# podlewacz_v4.net
KiCad netlist of a schematic drawn in EAGLE
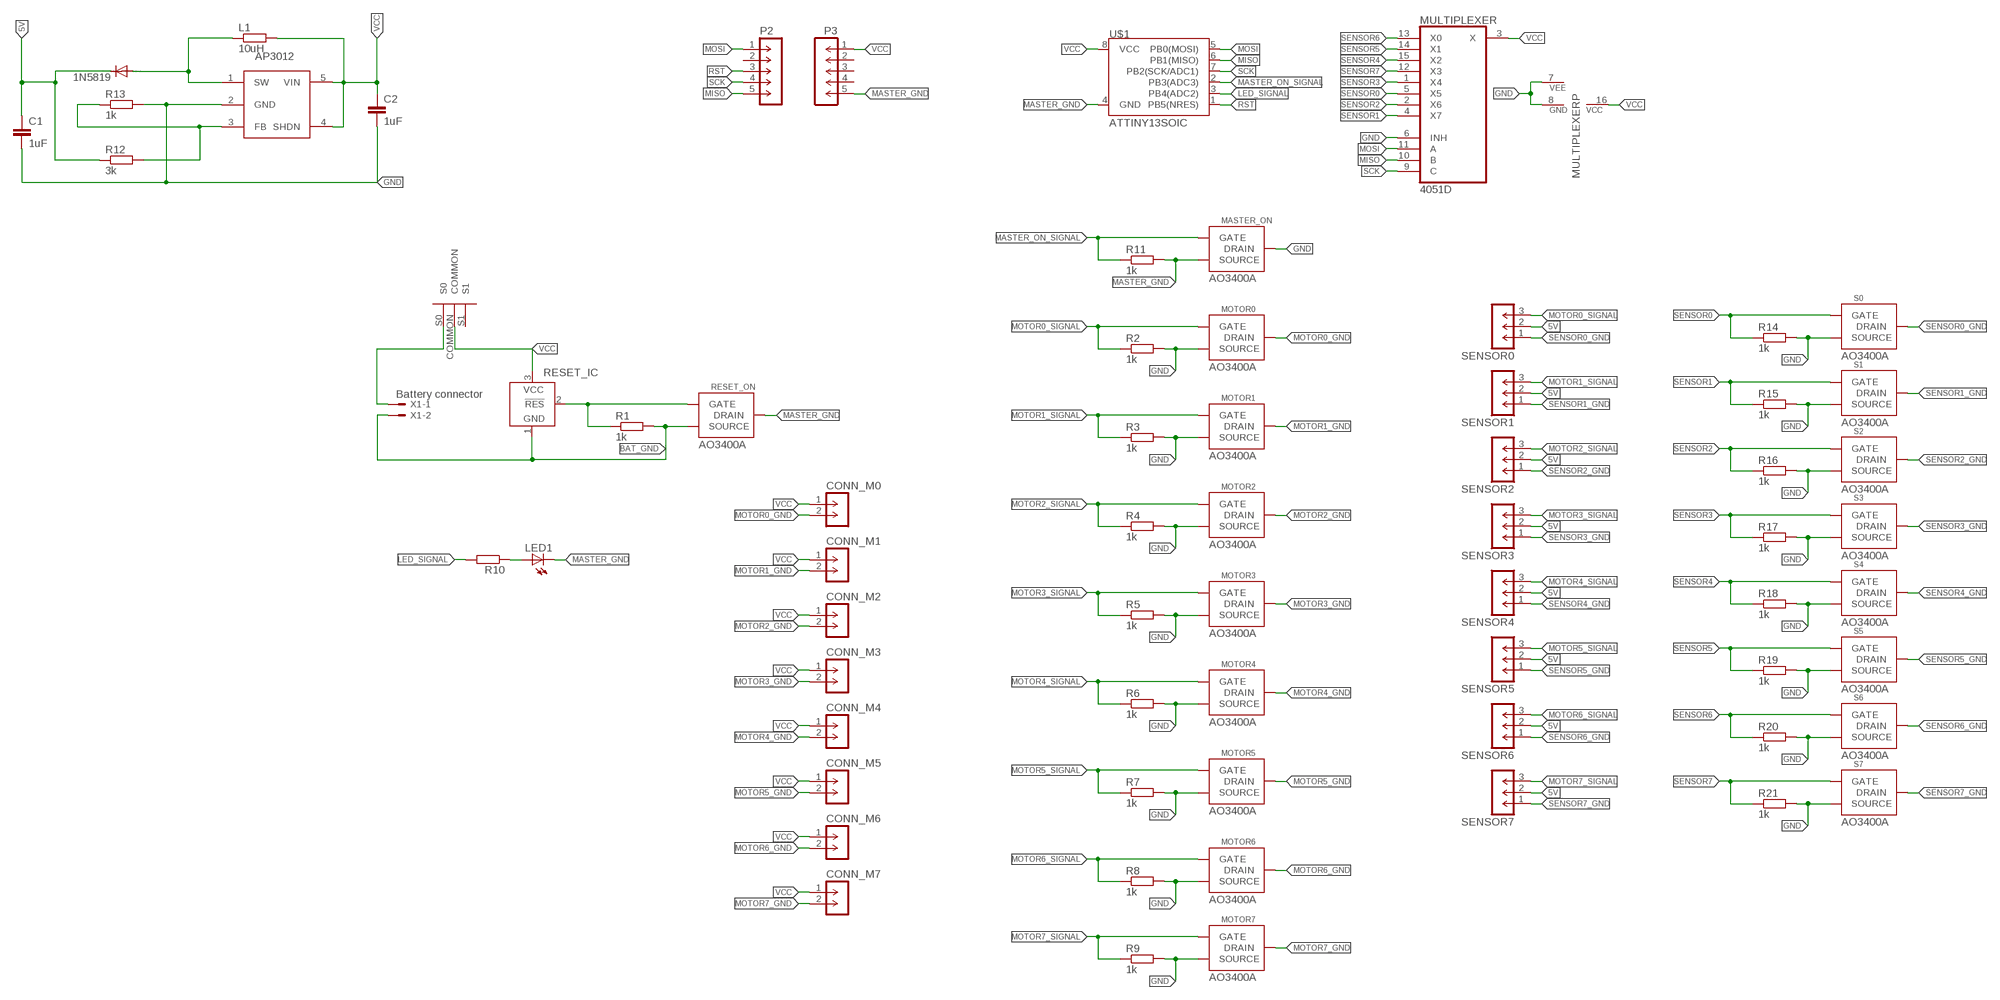
[diagram p0: schematic, sheet 1]

(export (version "E")
  (design (tool "Eeschema 10.0.6"))
  (components
    (comp (ref "1N5819")
      (value "DIODE-DO214AC")
      (footprint "eagle-import:DO214AC")
      (libsource (lib "eagle-import") (part "DIODE-DO214AC"))
    )
    (comp (ref "AP3012")
      (value "AP3012")
      (footprint "eagle-import:SOT-23-5")
      (libsource (lib "eagle-import") (part "AP3012"))
    )
    (comp (ref "C1")
      (value "1uF")
      (footprint "eagle-import:C1206")
      (libsource (lib "eagle-import") (part "C-EUC1206"))
    )
    (comp (ref "C2")
      (value "1uF")
      (footprint "eagle-import:C1206")
      (libsource (lib "eagle-import") (part "C-EUC1206"))
    )
    (comp (ref "CONN_M0")
      (value "M-1X02-SIP-100-32Y")
      (footprint "eagle-import:SIP-100-02-32Y")
      (libsource (lib "eagle-import") (part "M-1X02-SIP-100-32Y"))
    )
    (comp (ref "CONN_M1")
      (value "M-1X02-SIP-100-32Y")
      (footprint "eagle-import:SIP-100-02-32Y")
      (libsource (lib "eagle-import") (part "M-1X02-SIP-100-32Y"))
    )
    (comp (ref "CONN_M2")
      (value "M-1X02-SIP-100-32Y")
      (footprint "eagle-import:SIP-100-02-32Y")
      (libsource (lib "eagle-import") (part "M-1X02-SIP-100-32Y"))
    )
    (comp (ref "CONN_M3")
      (value "M-1X02-SIP-100-32Y")
      (footprint "eagle-import:SIP-100-02-32Y")
      (libsource (lib "eagle-import") (part "M-1X02-SIP-100-32Y"))
    )
    (comp (ref "CONN_M4")
      (value "M-1X02-SIP-100-32Y")
      (footprint "eagle-import:SIP-100-02-32Y")
      (libsource (lib "eagle-import") (part "M-1X02-SIP-100-32Y"))
    )
    (comp (ref "CONN_M5")
      (value "M-1X02-SIP-100-32Y")
      (footprint "eagle-import:SIP-100-02-32Y")
      (libsource (lib "eagle-import") (part "M-1X02-SIP-100-32Y"))
    )
    (comp (ref "CONN_M6")
      (value "M-1X02-SIP-100-32Y")
      (footprint "eagle-import:SIP-100-02-32Y")
      (libsource (lib "eagle-import") (part "M-1X02-SIP-100-32Y"))
    )
    (comp (ref "CONN_M7")
      (value "M-1X02-SIP-100-32Y")
      (footprint "eagle-import:SIP-100-02-32Y")
      (libsource (lib "eagle-import") (part "M-1X02-SIP-100-32Y"))
    )
    (comp (ref "L1")
      (value "10uH")
      (footprint "eagle-import:R0805")
      (libsource (lib "eagle-import") (part "R-EU_R0805"))
    )
    (comp (ref "LED1")
      (value "LEDCHIP-LED0805")
      (footprint "eagle-import:CHIP-LED0805")
      (libsource (lib "eagle-import") (part "LEDCHIP-LED0805"))
    )
    (comp (ref "MASTER_ON")
      (value "AO3400A")
      (footprint "eagle-import:SOT-23")
      (libsource (lib "eagle-import") (part "AO3400A"))
    )
    (comp (ref "MOTOR0")
      (value "AO3400A")
      (footprint "eagle-import:SOT-23")
      (libsource (lib "eagle-import") (part "AO3400A"))
    )
    (comp (ref "MOTOR1")
      (value "AO3400A")
      (footprint "eagle-import:SOT-23")
      (libsource (lib "eagle-import") (part "AO3400A"))
    )
    (comp (ref "MOTOR2")
      (value "AO3400A")
      (footprint "eagle-import:SOT-23")
      (libsource (lib "eagle-import") (part "AO3400A"))
    )
    (comp (ref "MOTOR3")
      (value "AO3400A")
      (footprint "eagle-import:SOT-23")
      (libsource (lib "eagle-import") (part "AO3400A"))
    )
    (comp (ref "MOTOR4")
      (value "AO3400A")
      (footprint "eagle-import:SOT-23")
      (libsource (lib "eagle-import") (part "AO3400A"))
    )
    (comp (ref "MOTOR5")
      (value "AO3400A")
      (footprint "eagle-import:SOT-23")
      (libsource (lib "eagle-import") (part "AO3400A"))
    )
    (comp (ref "MOTOR6")
      (value "AO3400A")
      (footprint "eagle-import:SOT-23")
      (libsource (lib "eagle-import") (part "AO3400A"))
    )
    (comp (ref "MOTOR7")
      (value "AO3400A")
      (footprint "eagle-import:SOT-23")
      (libsource (lib "eagle-import") (part "AO3400A"))
    )
    (comp (ref "MULTIPLEXER")
      (value "4051D")
      (footprint "eagle-import:SO16")
      (libsource (lib "eagle-import") (part "4051D"))
    )
    (comp (ref "P2")
      (value "M-1X05-SIP-100-32")
      (footprint "eagle-import:SIP-100-05-32")
      (libsource (lib "eagle-import") (part "M-1X05-SIP-100-32"))
    )
    (comp (ref "P3")
      (value "M-1X05-SIP-100-32")
      (footprint "eagle-import:SIP-100-05-32")
      (libsource (lib "eagle-import") (part "M-1X05-SIP-100-32"))
    )
    (comp (ref "R1")
      (value "1k")
      (footprint "eagle-import:M1206")
      (libsource (lib "eagle-import") (part "R-EU_M1206"))
    )
    (comp (ref "R2")
      (value "1k")
      (footprint "eagle-import:M1206")
      (libsource (lib "eagle-import") (part "R-EU_M1206"))
    )
    (comp (ref "R3")
      (value "1k")
      (footprint "eagle-import:M1206")
      (libsource (lib "eagle-import") (part "R-EU_M1206"))
    )
    (comp (ref "R4")
      (value "1k")
      (footprint "eagle-import:M1206")
      (libsource (lib "eagle-import") (part "R-EU_M1206"))
    )
    (comp (ref "R5")
      (value "1k")
      (footprint "eagle-import:M1206")
      (libsource (lib "eagle-import") (part "R-EU_M1206"))
    )
    (comp (ref "R6")
      (value "1k")
      (footprint "eagle-import:M1206")
      (libsource (lib "eagle-import") (part "R-EU_M1206"))
    )
    (comp (ref "R7")
      (value "1k")
      (footprint "eagle-import:M1206")
      (libsource (lib "eagle-import") (part "R-EU_M1206"))
    )
    (comp (ref "R8")
      (value "1k")
      (footprint "eagle-import:M1206")
      (libsource (lib "eagle-import") (part "R-EU_M1206"))
    )
    (comp (ref "R9")
      (value "1k")
      (footprint "eagle-import:M1206")
      (libsource (lib "eagle-import") (part "R-EU_M1206"))
    )
    (comp (ref "R10")
      (value "R-EU_M0805")
      (footprint "eagle-import:M0805")
      (libsource (lib "eagle-import") (part "R-EU_M0805"))
    )
    (comp (ref "R11")
      (value "1k")
      (footprint "eagle-import:M1206")
      (libsource (lib "eagle-import") (part "R-EU_M1206"))
    )
    (comp (ref "R12")
      (value "3k")
      (footprint "eagle-import:M1206")
      (libsource (lib "eagle-import") (part "R-EU_M1206"))
    )
    (comp (ref "R13")
      (value "1k")
      (footprint "eagle-import:M1206")
      (libsource (lib "eagle-import") (part "R-EU_M1206"))
    )
    (comp (ref "R14")
      (value "1k")
      (footprint "eagle-import:M1206")
      (libsource (lib "eagle-import") (part "R-EU_M1206"))
    )
    (comp (ref "R15")
      (value "1k")
      (footprint "eagle-import:M1206")
      (libsource (lib "eagle-import") (part "R-EU_M1206"))
    )
    (comp (ref "R16")
      (value "1k")
      (footprint "eagle-import:M1206")
      (libsource (lib "eagle-import") (part "R-EU_M1206"))
    )
    (comp (ref "R17")
      (value "1k")
      (footprint "eagle-import:M1206")
      (libsource (lib "eagle-import") (part "R-EU_M1206"))
    )
    (comp (ref "R18")
      (value "1k")
      (footprint "eagle-import:M1206")
      (libsource (lib "eagle-import") (part "R-EU_M1206"))
    )
    (comp (ref "R19")
      (value "1k")
      (footprint "eagle-import:M1206")
      (libsource (lib "eagle-import") (part "R-EU_M1206"))
    )
    (comp (ref "R20")
      (value "1k")
      (footprint "eagle-import:M1206")
      (libsource (lib "eagle-import") (part "R-EU_M1206"))
    )
    (comp (ref "R21")
      (value "1k")
      (footprint "eagle-import:M1206")
      (libsource (lib "eagle-import") (part "R-EU_M1206"))
    )
    (comp (ref "RESET_IC")
      (value "TCM809")
      (footprint "eagle-import:SOT23B-3")
      (fields (field (name "MF") "MICROCHIP") (field (name "MPN") "TCM809MENB713"))
      (libsource (lib "eagle-import") (part "TCM809"))
    )
    (comp (ref "RESET_ON")
      (value "AO3400A")
      (footprint "eagle-import:SOT-23")
      (libsource (lib "eagle-import") (part "AO3400A"))
    )
    (comp (ref "S0")
      (value "AO3400A")
      (footprint "eagle-import:SOT-23")
      (libsource (lib "eagle-import") (part "AO3400A"))
    )
    (comp (ref "S1")
      (value "AO3400A")
      (footprint "eagle-import:SOT-23")
      (libsource (lib "eagle-import") (part "AO3400A"))
    )
    (comp (ref "S2")
      (value "AO3400A")
      (footprint "eagle-import:SOT-23")
      (libsource (lib "eagle-import") (part "AO3400A"))
    )
    (comp (ref "S3")
      (value "AO3400A")
      (footprint "eagle-import:SOT-23")
      (libsource (lib "eagle-import") (part "AO3400A"))
    )
    (comp (ref "S4")
      (value "AO3400A")
      (footprint "eagle-import:SOT-23")
      (libsource (lib "eagle-import") (part "AO3400A"))
    )
    (comp (ref "S5")
      (value "AO3400A")
      (footprint "eagle-import:SOT-23")
      (libsource (lib "eagle-import") (part "AO3400A"))
    )
    (comp (ref "S6")
      (value "AO3400A")
      (footprint "eagle-import:SOT-23")
      (libsource (lib "eagle-import") (part "AO3400A"))
    )
    (comp (ref "S7")
      (value "AO3400A")
      (footprint "eagle-import:SOT-23")
      (libsource (lib "eagle-import") (part "AO3400A"))
    )
    (comp (ref "SENSOR0")
      (value "M-1X03-SIP-100-32Y")
      (footprint "eagle-import:SIP-100-03-32Y")
      (libsource (lib "eagle-import") (part "M-1X03-SIP-100-32Y"))
    )
    (comp (ref "SENSOR1")
      (value "M-1X03-SIP-100-32Y")
      (footprint "eagle-import:SIP-100-03-32Y")
      (libsource (lib "eagle-import") (part "M-1X03-SIP-100-32Y"))
    )
    (comp (ref "SENSOR2")
      (value "M-1X03-SIP-100-32Y")
      (footprint "eagle-import:SIP-100-03-32Y")
      (libsource (lib "eagle-import") (part "M-1X03-SIP-100-32Y"))
    )
    (comp (ref "SENSOR3")
      (value "M-1X03-SIP-100-32Y")
      (footprint "eagle-import:SIP-100-03-32Y")
      (libsource (lib "eagle-import") (part "M-1X03-SIP-100-32Y"))
    )
    (comp (ref "SENSOR4")
      (value "M-1X03-SIP-100-32Y")
      (footprint "eagle-import:SIP-100-03-32Y")
      (libsource (lib "eagle-import") (part "M-1X03-SIP-100-32Y"))
    )
    (comp (ref "SENSOR5")
      (value "M-1X03-SIP-100-32Y")
      (footprint "eagle-import:SIP-100-03-32Y")
      (libsource (lib "eagle-import") (part "M-1X03-SIP-100-32Y"))
    )
    (comp (ref "SENSOR6")
      (value "M-1X03-SIP-100-32Y")
      (footprint "eagle-import:SIP-100-03-32Y")
      (libsource (lib "eagle-import") (part "M-1X03-SIP-100-32Y"))
    )
    (comp (ref "SENSOR7")
      (value "M-1X03-SIP-100-32Y")
      (footprint "eagle-import:SIP-100-03-32Y")
      (libsource (lib "eagle-import") (part "M-1X03-SIP-100-32Y"))
    )
    (comp (ref "U$1")
      (value "ATTINY13SOIC")
      (footprint "eagle-import:SO08")
      (libsource (lib "eagle-import") (part "ATTINY13SOIC"))
    )
    (comp (ref "U$2")
      (value "SPDT_SLIDE_SWITCH_2_PITCH")
      (footprint "eagle-import:SPDT_SLIDE_SWITCH_2_PITCH")
      (libsource (lib "eagle-import") (part "SPDT_SLIDE_SWITCH_2_PITCH"))
    )
    (comp (ref "X1")
      (value "Battery connector")
      (footprint "eagle-import:22-23-2021")
      (fields (field (name "MF") "MOLEX") (field (name "MPN") "22-23-2021"))
      (libsource (lib "eagle-import") (part "22-23-2021"))
    )
  )
  (nets
    (net (code "1") (name "5V") (class "Default")
      (node (ref "1N5819") (pin "C") (pinfunction "C_C") (pintype "passive"))
      (node (ref "C1") (pin "1") (pinfunction "1_1") (pintype "passive"))
      (node (ref "R12") (pin "1") (pinfunction "1_1") (pintype "passive"))
      (node (ref "SENSOR0") (pin "2") (pinfunction "2_2") (pintype "passive"))
      (node (ref "SENSOR1") (pin "2") (pinfunction "2_2") (pintype "passive"))
      (node (ref "SENSOR2") (pin "2") (pinfunction "2_2") (pintype "passive"))
      (node (ref "SENSOR3") (pin "2") (pinfunction "2_2") (pintype "passive"))
      (node (ref "SENSOR4") (pin "2") (pinfunction "2_2") (pintype "passive"))
      (node (ref "SENSOR5") (pin "2") (pinfunction "2_2") (pintype "passive"))
      (node (ref "SENSOR6") (pin "2") (pinfunction "2_2") (pintype "passive"))
      (node (ref "SENSOR7") (pin "2") (pinfunction "2_2") (pintype "passive"))
    )
    (net (code "2") (name "BAT_GND") (class "Default")
      (node (ref "R1") (pin "2") (pinfunction "2_2") (pintype "passive"))
      (node (ref "RESET_IC") (pin "1") (pinfunction "GND_1") (pintype "power_in"))
      (node (ref "RESET_ON") (pin "2") (pinfunction "SOURCE_2") (pintype "bidirectional"))
      (node (ref "X1") (pin "2") (pinfunction "S_2") (pintype "passive"))
    )
    (net (code "3") (name "GND") (class "Default")
      (node (ref "AP3012") (pin "2") (pinfunction "GND_2") (pintype "bidirectional"))
      (node (ref "C1") (pin "2") (pinfunction "2_2") (pintype "passive"))
      (node (ref "C2") (pin "2") (pinfunction "2_2") (pintype "passive"))
      (node (ref "MASTER_ON") (pin "3") (pinfunction "DRAIN_3") (pintype "bidirectional"))
      (node (ref "MOTOR0") (pin "2") (pinfunction "SOURCE_2") (pintype "bidirectional"))
      (node (ref "MOTOR1") (pin "2") (pinfunction "SOURCE_2") (pintype "bidirectional"))
      (node (ref "MOTOR2") (pin "2") (pinfunction "SOURCE_2") (pintype "bidirectional"))
      (node (ref "MOTOR3") (pin "2") (pinfunction "SOURCE_2") (pintype "bidirectional"))
      (node (ref "MOTOR4") (pin "2") (pinfunction "SOURCE_2") (pintype "bidirectional"))
      (node (ref "MOTOR5") (pin "2") (pinfunction "SOURCE_2") (pintype "bidirectional"))
      (node (ref "MOTOR6") (pin "2") (pinfunction "SOURCE_2") (pintype "bidirectional"))
      (node (ref "MOTOR7") (pin "2") (pinfunction "SOURCE_2") (pintype "bidirectional"))
      (node (ref "MULTIPLEXER") (pin "6") (pinfunction "INH_6") (pintype "input"))
      (node (ref "MULTIPLEXER") (pin "7") (pinfunction "VEE_7") (pintype "power_in"))
      (node (ref "MULTIPLEXER") (pin "8") (pinfunction "GND_8") (pintype "power_in"))
      (node (ref "R13") (pin "2") (pinfunction "2_2") (pintype "passive"))
      (node (ref "R14") (pin "2") (pinfunction "2_2") (pintype "passive"))
      (node (ref "R15") (pin "2") (pinfunction "2_2") (pintype "passive"))
      (node (ref "R16") (pin "2") (pinfunction "2_2") (pintype "passive"))
      (node (ref "R17") (pin "2") (pinfunction "2_2") (pintype "passive"))
      (node (ref "R18") (pin "2") (pinfunction "2_2") (pintype "passive"))
      (node (ref "R19") (pin "2") (pinfunction "2_2") (pintype "passive"))
      (node (ref "R2") (pin "2") (pinfunction "2_2") (pintype "passive"))
      (node (ref "R20") (pin "2") (pinfunction "2_2") (pintype "passive"))
      (node (ref "R21") (pin "2") (pinfunction "2_2") (pintype "passive"))
      (node (ref "R3") (pin "2") (pinfunction "2_2") (pintype "passive"))
      (node (ref "R4") (pin "2") (pinfunction "2_2") (pintype "passive"))
      (node (ref "R5") (pin "2") (pinfunction "2_2") (pintype "passive"))
      (node (ref "R6") (pin "2") (pinfunction "2_2") (pintype "passive"))
      (node (ref "R7") (pin "2") (pinfunction "2_2") (pintype "passive"))
      (node (ref "R8") (pin "2") (pinfunction "2_2") (pintype "passive"))
      (node (ref "R9") (pin "2") (pinfunction "2_2") (pintype "passive"))
      (node (ref "S0") (pin "2") (pinfunction "SOURCE_2") (pintype "bidirectional"))
      (node (ref "S1") (pin "2") (pinfunction "SOURCE_2") (pintype "bidirectional"))
      (node (ref "S2") (pin "2") (pinfunction "SOURCE_2") (pintype "bidirectional"))
      (node (ref "S3") (pin "2") (pinfunction "SOURCE_2") (pintype "bidirectional"))
      (node (ref "S4") (pin "2") (pinfunction "SOURCE_2") (pintype "bidirectional"))
      (node (ref "S5") (pin "2") (pinfunction "SOURCE_2") (pintype "bidirectional"))
      (node (ref "S6") (pin "2") (pinfunction "SOURCE_2") (pintype "bidirectional"))
      (node (ref "S7") (pin "2") (pinfunction "SOURCE_2") (pintype "bidirectional"))
    )
    (net (code "4") (name "LED_SIGNAL") (class "Default")
      (node (ref "R10") (pin "2") (pinfunction "2_2") (pintype "passive"))
      (node (ref "U$1") (pin "3") (pinfunction "PB4(ADC2)_3") (pintype "bidirectional"))
    )
    (net (code "5") (name "MASTER_GND") (class "Default")
      (node (ref "LED1") (pin "C") (pinfunction "C_C") (pintype "passive"))
      (node (ref "MASTER_ON") (pin "2") (pinfunction "SOURCE_2") (pintype "bidirectional"))
      (node (ref "P3") (pin "5") (pinfunction "5_5") (pintype "passive"))
      (node (ref "R11") (pin "2") (pinfunction "2_2") (pintype "passive"))
      (node (ref "RESET_ON") (pin "3") (pinfunction "DRAIN_3") (pintype "bidirectional"))
      (node (ref "U$1") (pin "4") (pinfunction "GND_4") (pintype "bidirectional"))
    )
    (net (code "6") (name "MASTER_ON_SIGNAL") (class "Default")
      (node (ref "MASTER_ON") (pin "1") (pinfunction "GATE_1") (pintype "bidirectional"))
      (node (ref "R11") (pin "1") (pinfunction "1_1") (pintype "passive"))
      (node (ref "U$1") (pin "2") (pinfunction "PB3(ADC3)_2") (pintype "bidirectional"))
    )
    (net (code "7") (name "MISO") (class "Default")
      (node (ref "MULTIPLEXER") (pin "10") (pinfunction "B_10") (pintype "input"))
      (node (ref "P2") (pin "5") (pinfunction "5_5") (pintype "passive"))
      (node (ref "U$1") (pin "6") (pinfunction "PB1(MISO)_6") (pintype "bidirectional"))
    )
    (net (code "8") (name "MOSI") (class "Default")
      (node (ref "MULTIPLEXER") (pin "11") (pinfunction "A_11") (pintype "input"))
      (node (ref "P2") (pin "1") (pinfunction "1_1") (pintype "passive"))
      (node (ref "U$1") (pin "5") (pinfunction "PB0(MOSI)_5") (pintype "bidirectional"))
    )
    (net (code "9") (name "MOTOR0_GND") (class "Default")
      (node (ref "CONN_M0") (pin "2") (pinfunction "2_2") (pintype "passive"))
      (node (ref "MOTOR0") (pin "3") (pinfunction "DRAIN_3") (pintype "bidirectional"))
    )
    (net (code "10") (name "MOTOR0_SIGNAL") (class "Default")
      (node (ref "MOTOR0") (pin "1") (pinfunction "GATE_1") (pintype "bidirectional"))
      (node (ref "R2") (pin "1") (pinfunction "1_1") (pintype "passive"))
      (node (ref "SENSOR0") (pin "3") (pinfunction "3_3") (pintype "passive"))
    )
    (net (code "11") (name "MOTOR1_GND") (class "Default")
      (node (ref "CONN_M1") (pin "2") (pinfunction "2_2") (pintype "passive"))
      (node (ref "MOTOR1") (pin "3") (pinfunction "DRAIN_3") (pintype "bidirectional"))
    )
    (net (code "12") (name "MOTOR1_SIGNAL") (class "Default")
      (node (ref "MOTOR1") (pin "1") (pinfunction "GATE_1") (pintype "bidirectional"))
      (node (ref "R3") (pin "1") (pinfunction "1_1") (pintype "passive"))
      (node (ref "SENSOR1") (pin "3") (pinfunction "3_3") (pintype "passive"))
    )
    (net (code "13") (name "MOTOR2_GND") (class "Default")
      (node (ref "CONN_M2") (pin "2") (pinfunction "2_2") (pintype "passive"))
      (node (ref "MOTOR2") (pin "3") (pinfunction "DRAIN_3") (pintype "bidirectional"))
    )
    (net (code "14") (name "MOTOR2_SIGNAL") (class "Default")
      (node (ref "MOTOR2") (pin "1") (pinfunction "GATE_1") (pintype "bidirectional"))
      (node (ref "R4") (pin "1") (pinfunction "1_1") (pintype "passive"))
      (node (ref "SENSOR2") (pin "3") (pinfunction "3_3") (pintype "passive"))
    )
    (net (code "15") (name "MOTOR3_GND") (class "Default")
      (node (ref "CONN_M3") (pin "2") (pinfunction "2_2") (pintype "passive"))
      (node (ref "MOTOR3") (pin "3") (pinfunction "DRAIN_3") (pintype "bidirectional"))
    )
    (net (code "16") (name "MOTOR3_SIGNAL") (class "Default")
      (node (ref "MOTOR3") (pin "1") (pinfunction "GATE_1") (pintype "bidirectional"))
      (node (ref "R5") (pin "1") (pinfunction "1_1") (pintype "passive"))
      (node (ref "SENSOR3") (pin "3") (pinfunction "3_3") (pintype "passive"))
    )
    (net (code "17") (name "MOTOR4_GND") (class "Default")
      (node (ref "CONN_M4") (pin "2") (pinfunction "2_2") (pintype "passive"))
      (node (ref "MOTOR4") (pin "3") (pinfunction "DRAIN_3") (pintype "bidirectional"))
    )
    (net (code "18") (name "MOTOR4_SIGNAL") (class "Default")
      (node (ref "MOTOR4") (pin "1") (pinfunction "GATE_1") (pintype "bidirectional"))
      (node (ref "R6") (pin "1") (pinfunction "1_1") (pintype "passive"))
      (node (ref "SENSOR4") (pin "3") (pinfunction "3_3") (pintype "passive"))
    )
    (net (code "19") (name "MOTOR5_GND") (class "Default")
      (node (ref "CONN_M5") (pin "2") (pinfunction "2_2") (pintype "passive"))
      (node (ref "MOTOR5") (pin "3") (pinfunction "DRAIN_3") (pintype "bidirectional"))
    )
    (net (code "20") (name "MOTOR5_SIGNAL") (class "Default")
      (node (ref "MOTOR5") (pin "1") (pinfunction "GATE_1") (pintype "bidirectional"))
      (node (ref "R7") (pin "1") (pinfunction "1_1") (pintype "passive"))
      (node (ref "SENSOR5") (pin "3") (pinfunction "3_3") (pintype "passive"))
    )
    (net (code "21") (name "MOTOR6_GND") (class "Default")
      (node (ref "CONN_M6") (pin "2") (pinfunction "2_2") (pintype "passive"))
      (node (ref "MOTOR6") (pin "3") (pinfunction "DRAIN_3") (pintype "bidirectional"))
    )
    (net (code "22") (name "MOTOR6_SIGNAL") (class "Default")
      (node (ref "MOTOR6") (pin "1") (pinfunction "GATE_1") (pintype "bidirectional"))
      (node (ref "R8") (pin "1") (pinfunction "1_1") (pintype "passive"))
      (node (ref "SENSOR6") (pin "3") (pinfunction "3_3") (pintype "passive"))
    )
    (net (code "23") (name "MOTOR7_GND") (class "Default")
      (node (ref "CONN_M7") (pin "2") (pinfunction "2_2") (pintype "passive"))
      (node (ref "MOTOR7") (pin "3") (pinfunction "DRAIN_3") (pintype "bidirectional"))
    )
    (net (code "24") (name "MOTOR7_SIGNAL") (class "Default")
      (node (ref "MOTOR7") (pin "1") (pinfunction "GATE_1") (pintype "bidirectional"))
      (node (ref "R9") (pin "1") (pinfunction "1_1") (pintype "passive"))
      (node (ref "SENSOR7") (pin "3") (pinfunction "3_3") (pintype "passive"))
    )
    (net (code "25") (name "Net-(AP3012-FB)") (class "Default")
      (node (ref "AP3012") (pin "3") (pinfunction "FB_3") (pintype "bidirectional"))
      (node (ref "R12") (pin "2") (pinfunction "2_2") (pintype "passive"))
      (node (ref "R13") (pin "1") (pinfunction "1_1") (pintype "passive"))
    )
    (net (code "26") (name "Net-(AP3012-SW)") (class "Default")
      (node (ref "1N5819") (pin "A") (pinfunction "A_A") (pintype "passive"))
      (node (ref "AP3012") (pin "1") (pinfunction "SW_1") (pintype "bidirectional"))
      (node (ref "L1") (pin "1") (pinfunction "1_1") (pintype "passive"))
    )
    (net (code "27") (name "Net-(LED1-PadA)") (class "Default")
      (node (ref "LED1") (pin "A") (pinfunction "A_A") (pintype "passive"))
      (node (ref "R10") (pin "1") (pinfunction "1_1") (pintype "passive"))
    )
    (net (code "28") (name "Net-(RESET_IC-~{RES})") (class "Default")
      (node (ref "R1") (pin "1") (pinfunction "1_1") (pintype "passive"))
      (node (ref "RESET_IC") (pin "2") (pinfunction "~{RES}_2") (pintype "output"))
      (node (ref "RESET_ON") (pin "1") (pinfunction "GATE_1") (pintype "bidirectional"))
    )
    (net (code "29") (name "Net-(X1A-S)") (class "Default")
      (node (ref "U$2") (pin "S0") (pinfunction "S0_S0") (pintype "bidirectional"))
      (node (ref "X1") (pin "1") (pinfunction "S_1") (pintype "passive"))
    )
    (net (code "30") (name "RST") (class "Default")
      (node (ref "P2") (pin "3") (pinfunction "3_3") (pintype "passive"))
      (node (ref "U$1") (pin "1") (pinfunction "PB5(NRES)_1") (pintype "bidirectional"))
    )
    (net (code "31") (name "SCK") (class "Default")
      (node (ref "MULTIPLEXER") (pin "9") (pinfunction "C_9") (pintype "input"))
      (node (ref "P2") (pin "4") (pinfunction "4_4") (pintype "passive"))
      (node (ref "U$1") (pin "7") (pinfunction "PB2(SCK/ADC1)_7") (pintype "bidirectional"))
    )
    (net (code "32") (name "SENSOR0") (class "Default")
      (node (ref "MULTIPLEXER") (pin "5") (pinfunction "X5_5") (pintype "bidirectional"))
      (node (ref "R14") (pin "1") (pinfunction "1_1") (pintype "passive"))
      (node (ref "S0") (pin "1") (pinfunction "GATE_1") (pintype "bidirectional"))
    )
    (net (code "33") (name "SENSOR0_GND") (class "Default")
      (node (ref "S0") (pin "3") (pinfunction "DRAIN_3") (pintype "bidirectional"))
      (node (ref "SENSOR0") (pin "1") (pinfunction "1_1") (pintype "passive"))
    )
    (net (code "34") (name "SENSOR1") (class "Default")
      (node (ref "MULTIPLEXER") (pin "4") (pinfunction "X7_4") (pintype "bidirectional"))
      (node (ref "R15") (pin "1") (pinfunction "1_1") (pintype "passive"))
      (node (ref "S1") (pin "1") (pinfunction "GATE_1") (pintype "bidirectional"))
    )
    (net (code "35") (name "SENSOR1_GND") (class "Default")
      (node (ref "S1") (pin "3") (pinfunction "DRAIN_3") (pintype "bidirectional"))
      (node (ref "SENSOR1") (pin "1") (pinfunction "1_1") (pintype "passive"))
    )
    (net (code "36") (name "SENSOR2") (class "Default")
      (node (ref "MULTIPLEXER") (pin "2") (pinfunction "X6_2") (pintype "bidirectional"))
      (node (ref "R16") (pin "1") (pinfunction "1_1") (pintype "passive"))
      (node (ref "S2") (pin "1") (pinfunction "GATE_1") (pintype "bidirectional"))
    )
    (net (code "37") (name "SENSOR2_GND") (class "Default")
      (node (ref "S2") (pin "3") (pinfunction "DRAIN_3") (pintype "bidirectional"))
      (node (ref "SENSOR2") (pin "1") (pinfunction "1_1") (pintype "passive"))
    )
    (net (code "38") (name "SENSOR3") (class "Default")
      (node (ref "MULTIPLEXER") (pin "1") (pinfunction "X4_1") (pintype "bidirectional"))
      (node (ref "R17") (pin "1") (pinfunction "1_1") (pintype "passive"))
      (node (ref "S3") (pin "1") (pinfunction "GATE_1") (pintype "bidirectional"))
    )
    (net (code "39") (name "SENSOR3_GND") (class "Default")
      (node (ref "S3") (pin "3") (pinfunction "DRAIN_3") (pintype "bidirectional"))
      (node (ref "SENSOR3") (pin "1") (pinfunction "1_1") (pintype "passive"))
    )
    (net (code "40") (name "SENSOR4") (class "Default")
      (node (ref "MULTIPLEXER") (pin "15") (pinfunction "X2_15") (pintype "bidirectional"))
      (node (ref "R18") (pin "1") (pinfunction "1_1") (pintype "passive"))
      (node (ref "S4") (pin "1") (pinfunction "GATE_1") (pintype "bidirectional"))
    )
    (net (code "41") (name "SENSOR4_GND") (class "Default")
      (node (ref "S4") (pin "3") (pinfunction "DRAIN_3") (pintype "bidirectional"))
      (node (ref "SENSOR4") (pin "1") (pinfunction "1_1") (pintype "passive"))
    )
    (net (code "42") (name "SENSOR5") (class "Default")
      (node (ref "MULTIPLEXER") (pin "14") (pinfunction "X1_14") (pintype "bidirectional"))
      (node (ref "R19") (pin "1") (pinfunction "1_1") (pintype "passive"))
      (node (ref "S5") (pin "1") (pinfunction "GATE_1") (pintype "bidirectional"))
    )
    (net (code "43") (name "SENSOR5_GND") (class "Default")
      (node (ref "S5") (pin "3") (pinfunction "DRAIN_3") (pintype "bidirectional"))
      (node (ref "SENSOR5") (pin "1") (pinfunction "1_1") (pintype "passive"))
    )
    (net (code "44") (name "SENSOR6") (class "Default")
      (node (ref "MULTIPLEXER") (pin "13") (pinfunction "X0_13") (pintype "bidirectional"))
      (node (ref "R20") (pin "1") (pinfunction "1_1") (pintype "passive"))
      (node (ref "S6") (pin "1") (pinfunction "GATE_1") (pintype "bidirectional"))
    )
    (net (code "45") (name "SENSOR6_GND") (class "Default")
      (node (ref "S6") (pin "3") (pinfunction "DRAIN_3") (pintype "bidirectional"))
      (node (ref "SENSOR6") (pin "1") (pinfunction "1_1") (pintype "passive"))
    )
    (net (code "46") (name "SENSOR7") (class "Default")
      (node (ref "MULTIPLEXER") (pin "12") (pinfunction "X3_12") (pintype "bidirectional"))
      (node (ref "R21") (pin "1") (pinfunction "1_1") (pintype "passive"))
      (node (ref "S7") (pin "1") (pinfunction "GATE_1") (pintype "bidirectional"))
    )
    (net (code "47") (name "SENSOR7_GND") (class "Default")
      (node (ref "S7") (pin "3") (pinfunction "DRAIN_3") (pintype "bidirectional"))
      (node (ref "SENSOR7") (pin "1") (pinfunction "1_1") (pintype "passive"))
    )
    (net (code "48") (name "VCC") (class "Default")
      (node (ref "AP3012") (pin "4") (pinfunction "SHDN_4") (pintype "bidirectional"))
      (node (ref "AP3012") (pin "5") (pinfunction "VIN_5") (pintype "bidirectional"))
      (node (ref "C2") (pin "1") (pinfunction "1_1") (pintype "passive"))
      (node (ref "CONN_M0") (pin "1") (pinfunction "1_1") (pintype "passive"))
      (node (ref "CONN_M1") (pin "1") (pinfunction "1_1") (pintype "passive"))
      (node (ref "CONN_M2") (pin "1") (pinfunction "1_1") (pintype "passive"))
      (node (ref "CONN_M3") (pin "1") (pinfunction "1_1") (pintype "passive"))
      (node (ref "CONN_M4") (pin "1") (pinfunction "1_1") (pintype "passive"))
      (node (ref "CONN_M5") (pin "1") (pinfunction "1_1") (pintype "passive"))
      (node (ref "CONN_M6") (pin "1") (pinfunction "1_1") (pintype "passive"))
      (node (ref "CONN_M7") (pin "1") (pinfunction "1_1") (pintype "passive"))
      (node (ref "L1") (pin "2") (pinfunction "2_2") (pintype "passive"))
      (node (ref "MULTIPLEXER") (pin "16") (pinfunction "VCC_16") (pintype "power_in"))
      (node (ref "MULTIPLEXER") (pin "3") (pinfunction "X_3") (pintype "bidirectional"))
      (node (ref "P3") (pin "1") (pinfunction "1_1") (pintype "passive"))
      (node (ref "RESET_IC") (pin "3") (pinfunction "VCC_3") (pintype "power_in"))
      (node (ref "U$1") (pin "8") (pinfunction "VCC_8") (pintype "bidirectional"))
      (node (ref "U$2") (pin "COMMON") (pinfunction "COMMON_COMMON") (pintype "bidirectional"))
    )
    (net (code "49") (name "unconnected-(P2-Pad2)") (class "Default")
      (node (ref "P2") (pin "2") (pinfunction "2_2") (pintype "passive"))
    )
    (net (code "50") (name "unconnected-(P3-Pad2)") (class "Default")
      (node (ref "P3") (pin "2") (pinfunction "2_2") (pintype "passive"))
    )
    (net (code "51") (name "unconnected-(P3-Pad3)") (class "Default")
      (node (ref "P3") (pin "3") (pinfunction "3_3") (pintype "passive"))
    )
    (net (code "52") (name "unconnected-(P3-Pad4)") (class "Default")
      (node (ref "P3") (pin "4") (pinfunction "4_4") (pintype "passive"))
    )
    (net (code "53") (name "unconnected-(U$2-PadS1)") (class "Default")
      (node (ref "U$2") (pin "S1") (pinfunction "S1_S1") (pintype "bidirectional"))
    )
  )
)
